# 17-eMMC_FLASH_SDCARD_INTERFACE.net
KiCad netlist of a schematic drawn in Altium Designer
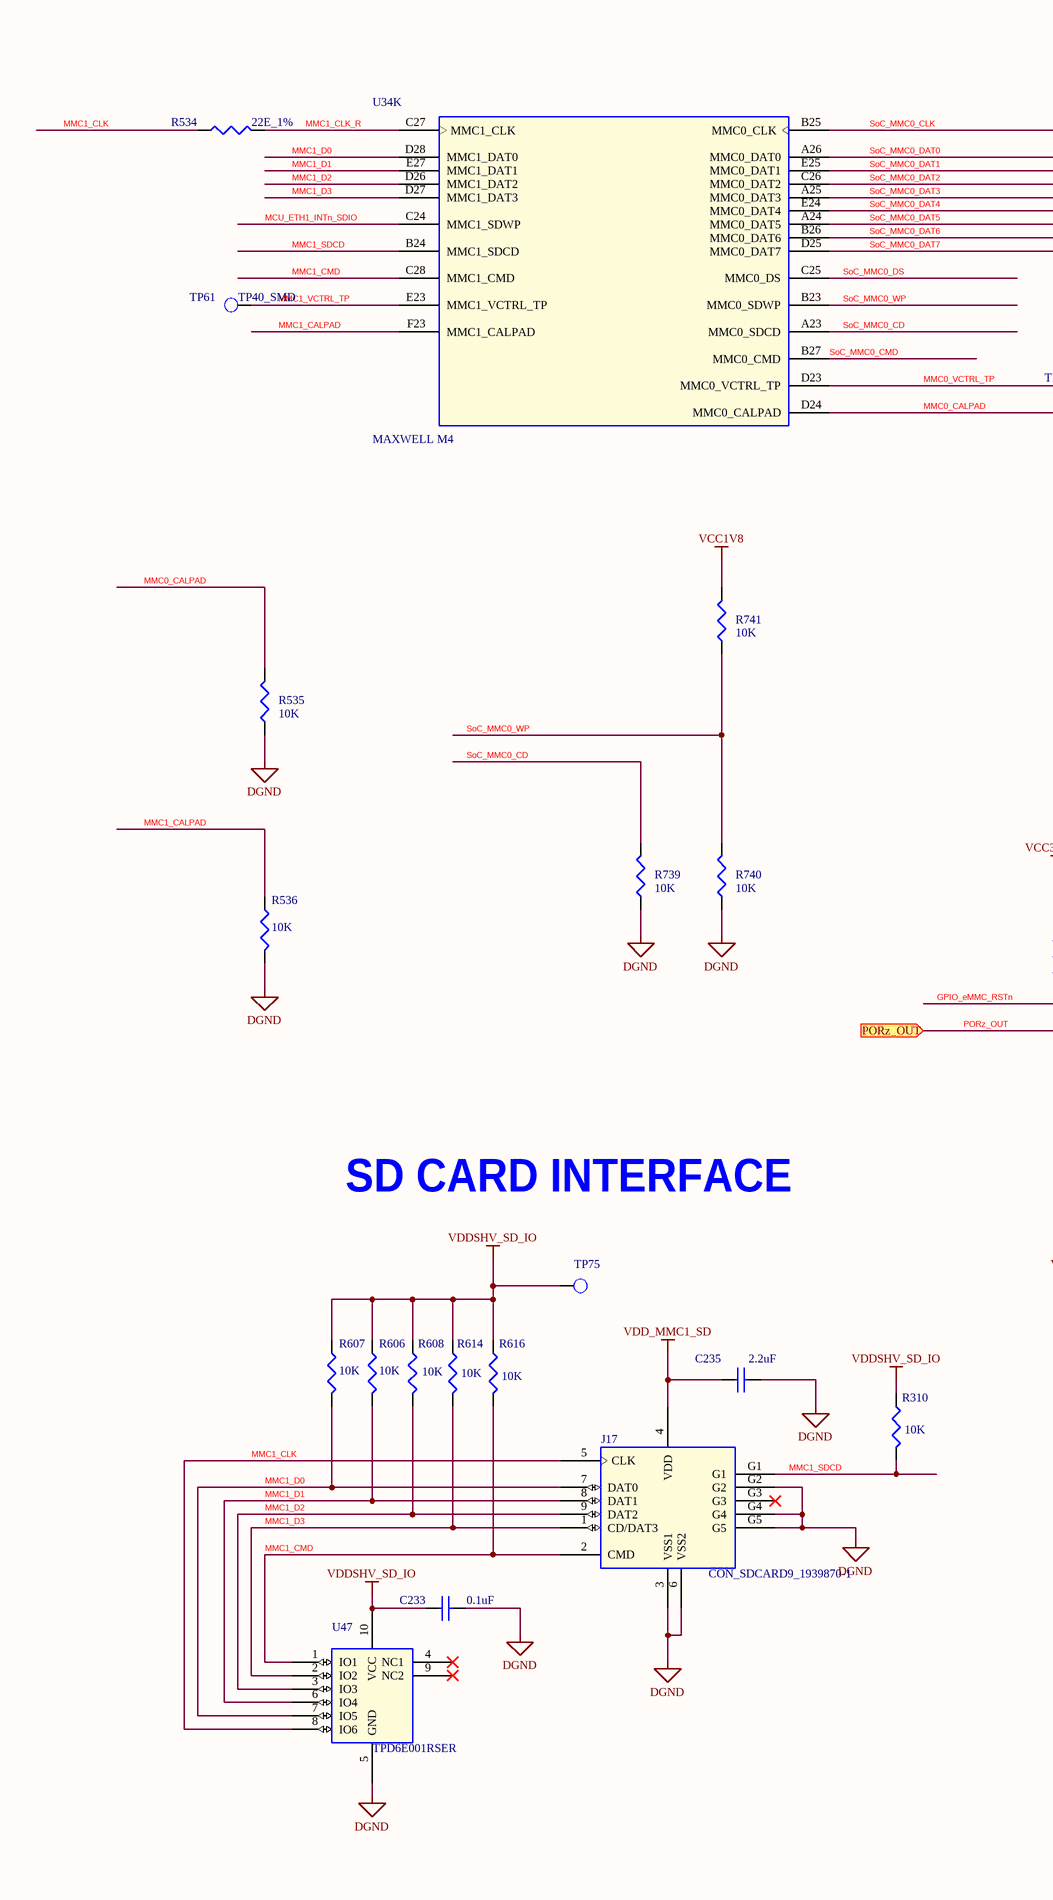
[diagram p0: 17-eMMC FLASH_SDCARD INTERFACE.SchDoc, left]
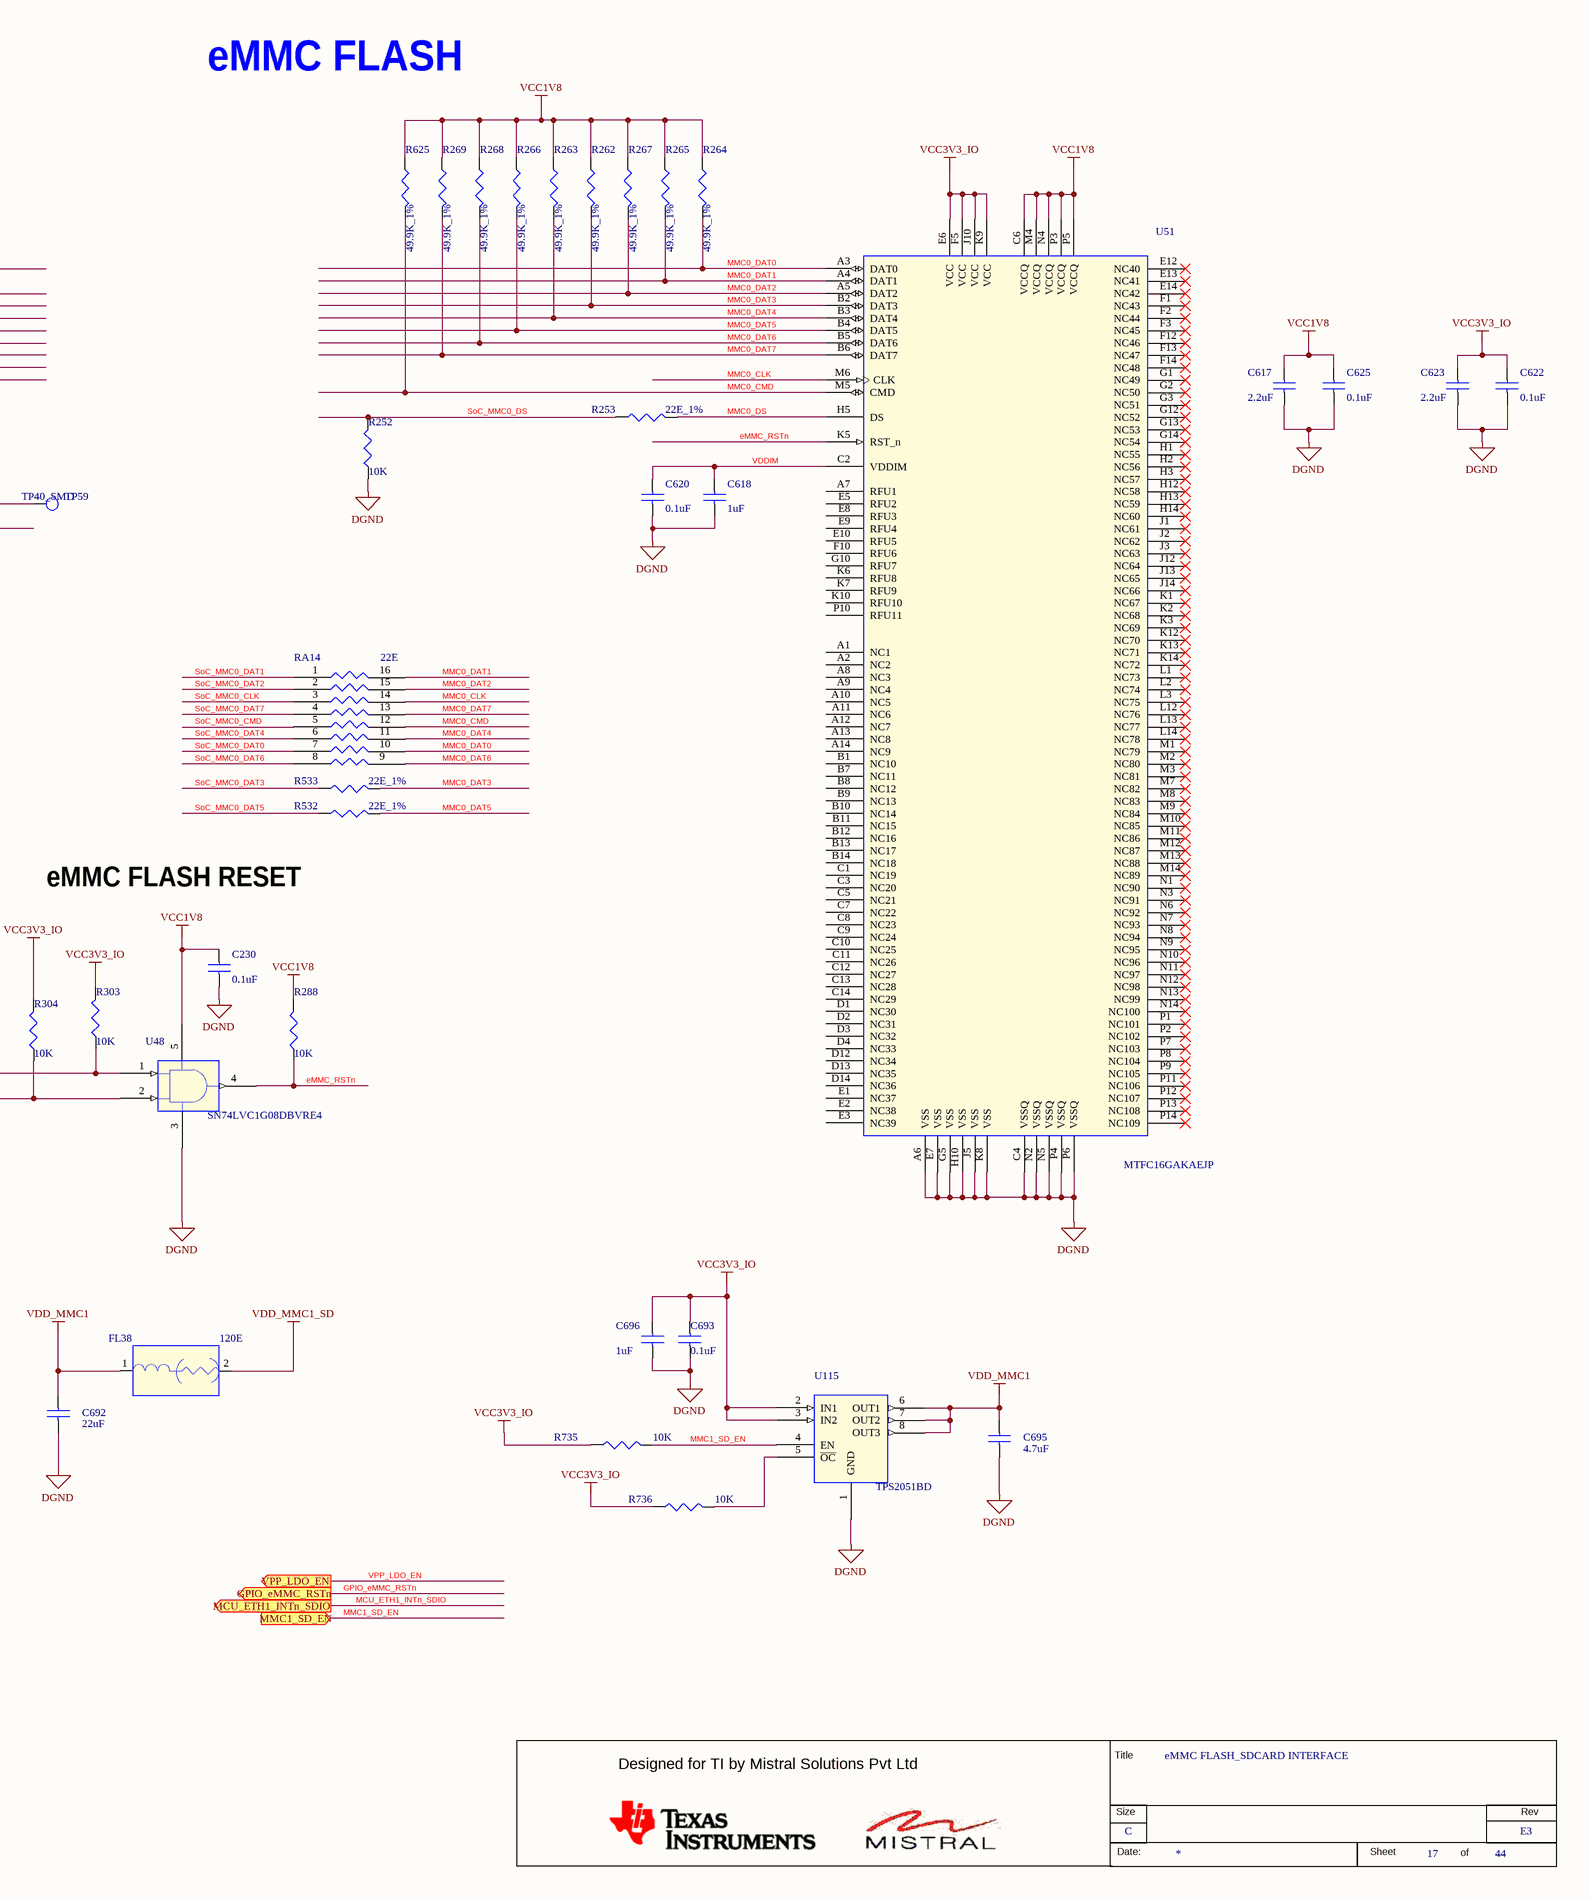
[diagram p1: 17-eMMC FLASH_SDCARD INTERFACE.SchDoc, right]

(export (version "E")
  (design (tool "Eeschema 10.0.6"))
  (components
    (comp (ref "C230")
      (value "0.1uF")
      (footprint "CAP0201_0-5")
      (description "CAP CERAMIC 0.1uF 16V 10% X5R 0201")
      (fields
        (field (name "MISTRAL PART NO") "120009030072-R")
        (field (name "MFR_PART_NUMBER") "GRM033R61C104KE84J")
      )
      (libsource (lib "*") (part "CAP_Dup5"))
    )
    (comp (ref "C233")
      (value "0.1uF")
      (footprint "CAP0201_0-5")
      (description "CAP CERAMIC 0.1uF 16V 10% X5R 0201")
      (fields (field (name "DISTRIBUTOR_PART_NUMBER") "490-16742-1-ND") (field (name "VOLTAGE") "16V"))
      (libsource (lib "*") (part "CAP_Dup5"))
    )
    (comp (ref "C235")
      (value "2.2uF")
      (footprint "CAP0402_0-75")
      (description "CAP CERAMIC 2.2uF 10V 20% X5R 0402")
      (fields
        (field (name "MISTRAL PART NO") "120018010016-R")
        (field (name "MFR_PART_NUMBER") "GRT155R61A225ME01D")
      )
      (libsource (lib "*") (part "CAP_Dup5"))
    )
    (comp (ref "C617")
      (value "2.2uF")
      (footprint "CAP0402_0-75")
      (description "CAP CERAMIC 2.2uF 10V 20% X5R 0402")
      (fields
        (field (name "MISTRAL PART NO") "120018010016-R")
        (field (name "MFR_PART_NUMBER") "GRT155R61A225ME01D")
      )
      (libsource (lib "*") (part "CAP_Dup5"))
    )
    (comp (ref "C618")
      (value "1uF")
      (footprint "CAP0402_0-75")
      (description "CAP CERAMIC 1uF 16V 20% X5R 0402")
      (fields (field (name "DISTRIBUTOR_PART_NUMBER") "587-5514-1-ND") (field (name "VOLTAGE") "16V"))
      (libsource (lib "*") (part "CAP_Dup5"))
    )
    (comp (ref "C620")
      (value "0.1uF")
      (footprint "CAP0201_0-5")
      (description "CAP CERAMIC 0.1uF 16V 10% X5R 0201")
      (fields
        (field (name "MISTRAL PART NO") "120009030072-R")
        (field (name "MFR_PART_NUMBER") "GRM033R61C104KE84J")
      )
      (libsource (lib "*") (part "CAP_Dup5"))
    )
    (comp (ref "C622")
      (value "0.1uF")
      (footprint "CAP0201_0-5")
      (description "CAP CERAMIC 0.1uF 16V 10% X5R 0201")
      (fields
        (field (name "MISTRAL PART NO") "120009030072-R")
        (field (name "MFR_PART_NUMBER") "GRM033R61C104KE84J")
      )
      (libsource (lib "*") (part "CAP_Dup5"))
    )
    (comp (ref "C623")
      (value "2.2uF")
      (footprint "CAP0402_0-75")
      (description "CAP CERAMIC 2.2uF 10V 20% X5R 0402")
      (fields
        (field (name "MISTRAL PART NO") "120018010016-R")
        (field (name "MFR_PART_NUMBER") "GRT155R61A225ME01D")
      )
      (libsource (lib "*") (part "CAP_Dup5"))
    )
    (comp (ref "C625")
      (value "0.1uF")
      (footprint "CAP0201_0-5")
      (description "CAP CERAMIC 0.1uF 16V 10% X5R 0201")
      (fields
        (field (name "MISTRAL PART NO") "120009030072-R")
        (field (name "MFR_PART_NUMBER") "GRM033R61C104KE84J")
      )
      (libsource (lib "*") (part "CAP_Dup5"))
    )
    (comp (ref "C692")
      (value "22uF")
      (footprint "CAP1206_2")
      (description "CAP CERAMIC 22uF 16V 20% X7R 1206")
      (fields (field (name "DISTRIBUTOR_PART_NUMBER") "587-4319-1-ND") (field (name "VOLTAGE") "16V"))
      (libsource (lib "*") (part "CAP_Dup5"))
    )
    (comp (ref "C693")
      (value "0.1uF")
      (footprint "CAP0201_0-5")
      (description "CAP CERAMIC 0.1uF 16V 10% X5R 0201")
      (fields (field (name "DISTRIBUTOR_PART_NUMBER") "490-16742-1-ND") (field (name "VOLTAGE") "16V"))
      (libsource (lib "*") (part "CAP_Dup5"))
    )
    (comp (ref "C695")
      (value "4.7uF")
      (footprint "CAP0402_0-75")
      (description "CAP CERAMIC 4.7uF 10V 20% X5R 0402")
      (fields
        (field (name "MISTRAL PART NO") "120012060002-R")
        (field (name "MFR_PART_NUMBER") "0402ZD475MAT2A")
      )
      (libsource (lib "*") (part "CAP_Dup5"))
    )
    (comp (ref "C696")
      (value "1uF")
      (footprint "CAP0402_0-75")
      (description "CAP CERAMIC 1uF 16V 20% X5R 0402")
      (fields (field (name "DISTRIBUTOR_PART_NUMBER") "587-5514-1-ND") (field (name "VOLTAGE") "16V"))
      (libsource (lib "*") (part "CAP_Dup5"))
    )
    (comp (ref "FL38")
      (value "120E")
      (footprint "EMIFIL_BLM15A_0402_0-6")
      (description "FERRITE CHIP 120E 1.3A 0402")
      (fields (field (name "DISTRIBUTOR_PART_NUMBER") "490-5203-1-ND") (field (name "VOLTAGE") "NA"))
      (libsource (lib "*") (part "EMIFILTER_IND"))
    )
    (comp (ref "J17")
      (value "CON_SDCARD9_1939870-1")
      (footprint "CON_SD9_1939870-1_S_R_S_2-9")
      (description "CON SD CARD PUSH-PUSH 9POS RT SMD")
      (fields (field (name "MISTRAL PART NO") "150017100004-R") (field (name "MFR_PART_NUMBER") "1939870-1"))
      (libsource (lib "*") (part "CON_SDCARD9_1939870-1"))
    )
    (comp (ref "R252")
      (value "10K")
      (footprint "RES0402_0-5")
      (description "RES 10K 1/16W 5% 0402")
      (fields (field (name "DISTRIBUTOR_PART_NUMBER") "311-10KJRCT-ND") (field (name "VOLTAGE") "NA"))
      (libsource (lib "*") (part "RESISTOR_Dup5"))
    )
    (comp (ref "R253")
      (value "22E_1%")
      (footprint "RES0402")
      (description "RES 22E 1/16W 1% 0402")
      (fields
        (field (name "CUST_PART_NUMBER") "4700-80047E")
        (field (name "DISTRIBUTOR_PART_NUMBER") "311-22.0LRCT-ND")
      )
      (libsource (lib "*") (part "RESISTOR_Dup4"))
    )
    (comp (ref "R262")
      (value "49.9K_1%")
      (footprint "RES0402")
      (description "RES 49.9K1/16W 1% 0402")
      (fields (field (name "DISTRIBUTOR_PART_NUMBER") "311-49.9KLRCT-ND") (field (name "TOLERANCE") "1%"))
      (libsource (lib "*") (part "RESISTOR_Dup5"))
    )
    (comp (ref "R263")
      (value "49.9K_1%")
      (footprint "RES0402")
      (description "RES 49.9K1/16W 1% 0402")
      (fields
        (field (name "MISTRAL PART NO") "110009030904-P")
        (field (name "MFR_PART_NUMBER") "RC0402FR-0749K9L")
      )
      (libsource (lib "*") (part "RESISTOR_Dup5"))
    )
    (comp (ref "R264")
      (value "49.9K_1%")
      (footprint "RES0402")
      (description "RES 49.9K1/16W 1% 0402")
      (fields
        (field (name "MISTRAL PART NO") "110009030904-P")
        (field (name "MFR_PART_NUMBER") "RC0402FR-0749K9L")
      )
      (libsource (lib "*") (part "RESISTOR_Dup5"))
    )
    (comp (ref "R265")
      (value "49.9K_1%")
      (footprint "RES0402")
      (description "RES 49.9K1/16W 1% 0402")
      (fields
        (field (name "MISTRAL PART NO") "110009030904-P")
        (field (name "MFR_PART_NUMBER") "RC0402FR-0749K9L")
      )
      (libsource (lib "*") (part "RESISTOR_Dup5"))
    )
    (comp (ref "R266")
      (value "49.9K_1%")
      (footprint "RES0402")
      (description "RES 49.9K1/16W 1% 0402")
      (fields (field (name "DISTRIBUTOR_PART_NUMBER") "311-49.9KLRCT-ND") (field (name "TOLERANCE") "1%"))
      (libsource (lib "*") (part "RESISTOR_Dup5"))
    )
    (comp (ref "R267")
      (value "49.9K_1%")
      (footprint "RES0402")
      (description "RES 49.9K1/16W 1% 0402")
      (fields (field (name "DISTRIBUTOR_PART_NUMBER") "311-49.9KLRCT-ND") (field (name "TOLERANCE") "1%"))
      (libsource (lib "*") (part "RESISTOR_Dup5"))
    )
    (comp (ref "R268")
      (value "49.9K_1%")
      (footprint "RES0402")
      (description "RES 49.9K1/16W 1% 0402")
      (fields
        (field (name "MISTRAL PART NO") "110009030904-P")
        (field (name "MFR_PART_NUMBER") "RC0402FR-0749K9L")
      )
      (libsource (lib "*") (part "RESISTOR_Dup5"))
    )
    (comp (ref "R269")
      (value "49.9K_1%")
      (footprint "RES0402")
      (description "RES 49.9K1/16W 1% 0402")
      (fields (field (name "DISTRIBUTOR_PART_NUMBER") "311-49.9KLRCT-ND") (field (name "TOLERANCE") "1%"))
      (libsource (lib "*") (part "RESISTOR_Dup5"))
    )
    (comp (ref "R288")
      (value "10K")
      (footprint "RES0402_0-5")
      (description "RES 10K 1/16W 5% 0402")
      (fields (field (name "DISTRIBUTOR_PART_NUMBER") "311-10KJRCT-ND") (field (name "VOLTAGE") "NA"))
      (libsource (lib "*") (part "RESISTOR_Dup5"))
    )
    (comp (ref "R303")
      (value "10K")
      (footprint "RES0402_0-5")
      (description "RES 10K 1/16W 5% 0402")
      (fields
        (field (name "MISTRAL PART NO") "110009030208-R")
        (field (name "MFR_PART_NUMBER") "RC0402JR-0710KL")
      )
      (libsource (lib "*") (part "RESISTOR_Dup5"))
    )
    (comp (ref "R304")
      (value "10K")
      (footprint "RES0402_0-5")
      (description "RES 10K 1/16W 5% 0402")
      (fields
        (field (name "MISTRAL PART NO") "110009030208-R")
        (field (name "MFR_PART_NUMBER") "RC0402JR-0710KL")
      )
      (libsource (lib "*") (part "RESISTOR_Dup5"))
    )
    (comp (ref "R310")
      (value "10K")
      (footprint "RES0402_0-5")
      (description "RES 10K 1/16W 5% 0402")
      (fields (field (name "DISTRIBUTOR_PART_NUMBER") "311-10KJRCT-ND") (field (name "VOLTAGE") "NA"))
      (libsource (lib "*") (part "RESISTOR_Dup5"))
    )
    (comp (ref "R532")
      (value "22E_1%")
      (footprint "RES0402")
      (description "RES 22E 1/16W 1% 0402")
      (fields
        (field (name "CUST_PART_NUMBER") "4700-80047E")
        (field (name "DISTRIBUTOR_PART_NUMBER") "311-22.0LRCT-ND")
      )
      (libsource (lib "*") (part "RESISTOR_Dup4"))
    )
    (comp (ref "R533")
      (value "22E_1%")
      (footprint "RES0402")
      (description "RES 22E 1/16W 1% 0402")
      (fields
        (field (name "CUST_PART_NUMBER") "4700-80047E")
        (field (name "DISTRIBUTOR_PART_NUMBER") "311-22.0LRCT-ND")
      )
      (libsource (lib "*") (part "RESISTOR_Dup4"))
    )
    (comp (ref "R534")
      (value "22E_1%")
      (footprint "RES0402")
      (description "RES 22E 1/16W 1% 0402")
      (fields
        (field (name "MISTRAL PART NO") "110009090004-P")
        (field (name "MFR_PART_NUMBER") "RC0402FR-0722RL")
      )
      (libsource (lib "*") (part "RESISTOR_Dup5"))
    )
    (comp (ref "R535")
      (value "10K")
      (footprint "RES0402_0-5")
      (description "RES 10K 1/16W 5% 0402")
      (fields (field (name "DISTRIBUTOR_PART_NUMBER") "311-10KJRCT-ND") (field (name "VOLTAGE") "NA"))
      (libsource (lib "*") (part "RESISTOR_Dup5"))
    )
    (comp (ref "R536")
      (value "10K")
      (footprint "RES0402_0-5")
      (description "RES 10K 1/16W 5% 0402")
      (fields
        (field (name "MISTRAL PART NO") "110009030208-R")
        (field (name "MFR_PART_NUMBER") "RC0402JR-0710KL")
      )
      (libsource (lib "*") (part "RESISTOR_Dup5"))
    )
    (comp (ref "R606")
      (value "10K")
      (footprint "RES0402_0-5")
      (description "RES 10K 1/16W 5% 0402")
      (fields
        (field (name "MISTRAL PART NO") "110009030208-R")
        (field (name "MFR_PART_NUMBER") "RC0402JR-0710KL")
      )
      (libsource (lib "*") (part "RESISTOR_Dup5"))
    )
    (comp (ref "R607")
      (value "10K")
      (footprint "RES0402_0-5")
      (description "RES 10K 1/16W 5% 0402")
      (fields
        (field (name "MISTRAL PART NO") "110009030208-R")
        (field (name "MFR_PART_NUMBER") "RC0402JR-0710KL")
      )
      (libsource (lib "*") (part "RESISTOR_Dup5"))
    )
    (comp (ref "R608")
      (value "10K")
      (footprint "RES0402_0-5")
      (description "RES 10K 1/16W 5% 0402")
      (fields (field (name "DISTRIBUTOR_PART_NUMBER") "311-10KJRCT-ND") (field (name "VOLTAGE") "NA"))
      (libsource (lib "*") (part "RESISTOR_Dup5"))
    )
    (comp (ref "R614")
      (value "10K")
      (footprint "RES0402_0-5")
      (description "RES 10K 1/16W 5% 0402")
      (fields (field (name "DISTRIBUTOR_PART_NUMBER") "311-10KJRCT-ND") (field (name "VOLTAGE") "NA"))
      (libsource (lib "*") (part "RESISTOR_Dup5"))
    )
    (comp (ref "R616")
      (value "10K")
      (footprint "RES0402_0-5")
      (description "RES 10K 1/16W 5% 0402")
      (fields
        (field (name "MISTRAL PART NO") "110009030208-R")
        (field (name "MFR_PART_NUMBER") "RC0402JR-0710KL")
      )
      (libsource (lib "*") (part "RESISTOR_Dup5"))
    )
    (comp (ref "R625")
      (value "49.9K_1%")
      (footprint "RES0402")
      (description "RES 49.9K1/16W 1% 0402")
      (fields
        (field (name "MISTRAL PART NO") "110009030904-P")
        (field (name "MFR_PART_NUMBER") "RC0402FR-0749K9L")
      )
      (libsource (lib "*") (part "RESISTOR_Dup5"))
    )
    (comp (ref "R735")
      (value "10K")
      (footprint "RES0402_0-5")
      (description "RES 10K 1/16W 5% 0402")
      (fields
        (field (name "MISTRAL PART NO") "110009030208-R")
        (field (name "MFR_PART_NUMBER") "RC0402JR-0710KL")
      )
      (libsource (lib "*") (part "RESISTOR_Dup5"))
    )
    (comp (ref "R736")
      (value "10K")
      (footprint "RES0402_0-5")
      (description "RES 10K 1/16W 5% 0402")
      (fields (field (name "DISTRIBUTOR_PART_NUMBER") "311-10KJRCT-ND") (field (name "VOLTAGE") "NA"))
      (libsource (lib "*") (part "RESISTOR_Dup5"))
    )
    (comp (ref "R739")
      (value "10K")
      (footprint "RES0402_0-5")
      (description "RES 10K 1/16W 5% 0402")
      (fields (field (name "DISTRIBUTOR_PART_NUMBER") "311-10KJRCT-ND") (field (name "VOLTAGE") "NA"))
      (libsource (lib "*") (part "RESISTOR_Dup5"))
    )
    (comp (ref "R740")
      (value "10K")
      (footprint "RES0402_0-5")
      (description "RES 10K 1/16W 5% 0402")
      (fields (field (name "DISTRIBUTOR_PART_NUMBER") "311-10KJRCT-ND") (field (name "VOLTAGE") "NA"))
      (libsource (lib "*") (part "RESISTOR_Dup5"))
    )
    (comp (ref "R741")
      (value "10K")
      (footprint "RES0402_0-5")
      (description "RES 10K 1/16W 5% 0402")
      (fields (field (name "DISTRIBUTOR_PART_NUMBER") "311-10KJRCT-ND") (field (name "VOLTAGE") "NA"))
      (libsource (lib "*") (part "RESISTOR_Dup5"))
    )
    (comp (ref "RA14")
      (value "22E")
      (footprint "RESA_0402-8")
      (description "RES ARRAY 22E 62.5mW 5% 0402")
      (fields
        (field (name "MISTRAL PART NO") "110009030020-R")
        (field (name "MFR_PART_NUMBER") "741X163220JP")
      )
      (libsource (lib "*") (part "RESARR_ISO8"))
    )
    (comp (ref "TP59")
      (value "TP40_SMD")
      (footprint "TP40_SMD")
      (description "TESTPOINT CIR 40 SMD")
      (fields (field (name "VOLTAGE") "NA") (field (name "MISTRAL PART NO") "130009030933"))
      (libsource (lib "*") (part "TESTPOINT"))
    )
    (comp (ref "TP61")
      (value "TP40_SMD")
      (footprint "TP40_SMD")
      (description "TESTPOINT CIR 40 SMD")
      (fields (field (name "VOLTAGE") "NA") (field (name "MISTRAL PART NO") "130009030933"))
      (libsource (lib "*") (part "TESTPOINT"))
    )
    (comp (ref "TP75")
      (value "TP40_SMD")
      (footprint "TP40_SMD")
      (description "TESTPOINT CIR 40 SMD")
      (fields (field (name "MISTRAL PART NO") "130009030933") (field (name "DISTRIBUTOR_PART_NUMBER") "NA"))
      (libsource (lib "*") (part "TESTPOINT"))
    )
    (comp (ref "U34")
      (value "MAXWELL M4")
      (footprint "BGA784_31-49_910X910_1-7")
      (description "IC MAXWELL MICRO CONTROLLER UNIT BGA784")
      (fields (field (name "DISTRIBUTOR_PART_NUMBER") "NA") (field (name "MFR_PART_NUMBER") "MAXWELL M4_EVM"))
      (libsource (lib "*") (part "AM654X_BGA784"))
    )
    (comp (ref "U47")
      (value "TPD6E001RSER")
      (footprint "UQFN10_19-68_80X60_0-6")
      (description "IC 6CH ESD-PROTECTION ARRAY UQFN10")
      (fields
        (field (name "MISTRAL PART NO") "141011080020-R")
        (field (name "TOLERANCE") "NA")
        (field (name "LIBRARY PATH") "Y~{:}MIS_DATABAS~{E}Librar~{y}ALTIUM_TOO~{L}SCHEMATICS_PART~{S}MS_MISCINTERFACE_Library.schlib")
      )
      (libsource (lib "*") (part "TPD6E001RSE_UQFN10"))
    )
    (comp (ref "U48")
      (value "SN74LVC1G08DBVRE4")
      (footprint "SOT23-5")
      (description "IC SINGLE 2-INPUT POSITIVE AND GATE SOT23-5")
      (fields
        (field (name "MISTRAL PART NO") "141009060026-R")
        (field (name "DISTRIBUTOR_PART_NUMBER") "SN74LVC1G08DBVRE4-ND")
      )
      (libsource (lib "*") (part "SN74LVC1G08DBVRE4_SOT23-5"))
    )
    (comp (ref "U51")
      (value "MTFC16GAKAEJP")
      (footprint "VFBGA153_19-68_460X520_1-2")
      (description "IC 16GB E-MMC MEMORY VFBGA153")
      (fields
        (field (name "MISTRAL PART NO") "141118010003-R")
        (field (name "MFR_PART_NUMBER") "MTFC16GAKAEJP-4M IT")
      )
      (libsource (lib "*") (part "MTFC16GAKAEJP_VFBGA153"))
    )
    (comp (ref "U115")
      (value "TPS2051BD")
      (footprint "SOIC8_1-8")
      (description "IC POWER DISTRIBUTION SWITCH SOIC8")
      (fields
        (field (name "MISTRAL PART NO") "142014060011-R")
        (field (name "TOLERANCE") "NA")
        (field (name "LIBRARY PATH") "Y~{:}MIS_DATABAS~{E}Librar~{y}ALTIUM_TOO~{L}SCHEMATICS_PART~{S}MS_MISCPOWER_Library.schlib")
      )
      (libsource (lib "*") (part "TPS2051BD_SOIC8"))
    )
  )
  (nets
    (net (code "1") (name "/GPIO_eMMC_RSTn") (class "Default")
      (node (ref "R303") (pin "1") (pinfunction "1_1") (pintype "passive"))
      (node (ref "U48") (pin "1") (pinfunction "A_1") (pintype "input"))
    )
    (net (code "2") (name "/MCU_ETH1_INTn_SDIO") (class "Default")
      (node (ref "U34") (pin "C24") (pinfunction "MMC1_SDWP_C24") (pintype "passive"))
    )
    (net (code "3") (name "/MMC0_CALPAD") (class "Default")
      (node (ref "R535") (pin "1") (pinfunction "1_1") (pintype "passive"))
      (node (ref "U34") (pin "D24") (pinfunction "MMC0_CALPAD_D24") (pintype "passive"))
    )
    (net (code "4") (name "/MMC0_CLK") (class "Default")
      (node (ref "RA14") (pin "14") (pinfunction "14_14") (pintype "passive"))
      (node (ref "U51") (pin "M6") (pinfunction "CLK_M6") (pintype "input"))
    )
    (net (code "5") (name "/MMC0_CMD") (class "Default")
      (node (ref "R625") (pin "2") (pinfunction "2_2") (pintype "passive"))
      (node (ref "RA14") (pin "12") (pinfunction "12_12") (pintype "passive"))
      (node (ref "U51") (pin "M5") (pinfunction "CMD_M5") (pintype "bidirectional"))
    )
    (net (code "6") (name "/MMC0_DAT0") (class "Default")
      (node (ref "R264") (pin "2") (pinfunction "2_2") (pintype "passive"))
      (node (ref "RA14") (pin "10") (pinfunction "10_10") (pintype "passive"))
      (node (ref "U51") (pin "A3") (pinfunction "DAT0_A3") (pintype "bidirectional"))
    )
    (net (code "7") (name "/MMC0_DAT1") (class "Default")
      (node (ref "R265") (pin "2") (pinfunction "2_2") (pintype "passive"))
      (node (ref "RA14") (pin "16") (pinfunction "16_16") (pintype "passive"))
      (node (ref "U51") (pin "A4") (pinfunction "DAT1_A4") (pintype "bidirectional"))
    )
    (net (code "8") (name "/MMC0_DAT2") (class "Default")
      (node (ref "R267") (pin "2") (pinfunction "2_2") (pintype "passive"))
      (node (ref "RA14") (pin "15") (pinfunction "15_15") (pintype "passive"))
      (node (ref "U51") (pin "A5") (pinfunction "DAT2_A5") (pintype "bidirectional"))
    )
    (net (code "9") (name "/MMC0_DAT3") (class "Default")
      (node (ref "R262") (pin "2") (pinfunction "2_2") (pintype "passive"))
      (node (ref "R533") (pin "2") (pinfunction "2_2") (pintype "passive"))
      (node (ref "U51") (pin "B2") (pinfunction "DAT3_B2") (pintype "bidirectional"))
    )
    (net (code "10") (name "/MMC0_DAT4") (class "Default")
      (node (ref "R263") (pin "2") (pinfunction "2_2") (pintype "passive"))
      (node (ref "RA14") (pin "11") (pinfunction "11_11") (pintype "passive"))
      (node (ref "U51") (pin "B3") (pinfunction "DAT4_B3") (pintype "bidirectional"))
    )
    (net (code "11") (name "/MMC0_DAT5") (class "Default")
      (node (ref "R266") (pin "2") (pinfunction "2_2") (pintype "passive"))
      (node (ref "R532") (pin "2") (pinfunction "2_2") (pintype "passive"))
      (node (ref "U51") (pin "B4") (pinfunction "DAT5_B4") (pintype "bidirectional"))
    )
    (net (code "12") (name "/MMC0_DAT6") (class "Default")
      (node (ref "R268") (pin "2") (pinfunction "2_2") (pintype "passive"))
      (node (ref "RA14") (pin "9") (pinfunction "9_9") (pintype "passive"))
      (node (ref "U51") (pin "B5") (pinfunction "DAT6_B5") (pintype "bidirectional"))
    )
    (net (code "13") (name "/MMC0_DAT7") (class "Default")
      (node (ref "R269") (pin "2") (pinfunction "2_2") (pintype "passive"))
      (node (ref "RA14") (pin "13") (pinfunction "13_13") (pintype "passive"))
      (node (ref "U51") (pin "B6") (pinfunction "DAT7_B6") (pintype "bidirectional"))
    )
    (net (code "14") (name "/MMC0_DS") (class "Default")
      (node (ref "R253") (pin "2") (pinfunction "2_2") (pintype "passive"))
      (node (ref "U51") (pin "H5") (pinfunction "DS_H5") (pintype "passive"))
    )
    (net (code "15") (name "/MMC0_VCTRL_TP") (class "Default")
      (node (ref "TP59") (pin "1") (pinfunction "TP_1") (pintype "passive"))
      (node (ref "U34") (pin "D23") (pinfunction "MMC0_VCTRL_TP_D23") (pintype "passive"))
    )
    (net (code "16") (name "/MMC1_CALPAD") (class "Default")
      (node (ref "R536") (pin "1") (pinfunction "1_1") (pintype "passive"))
      (node (ref "U34") (pin "F23") (pinfunction "MMC1_CALPAD_F23") (pintype "passive"))
    )
    (net (code "17") (name "/MMC1_CLK") (class "Default")
      (node (ref "J17") (pin "5") (pinfunction "CLK_5") (pintype "passive"))
      (node (ref "R534") (pin "1") (pinfunction "1_1") (pintype "passive"))
      (node (ref "U47") (pin "8") (pinfunction "IO6_8") (pintype "bidirectional"))
    )
    (net (code "18") (name "/MMC1_CLK_R") (class "Default")
      (node (ref "R534") (pin "2") (pinfunction "2_2") (pintype "passive"))
      (node (ref "U34") (pin "C27") (pinfunction "MMC1_CLK_C27") (pintype "passive"))
    )
    (net (code "19") (name "/MMC1_CMD") (class "Default")
      (node (ref "J17") (pin "2") (pinfunction "CMD_2") (pintype "passive"))
      (node (ref "R616") (pin "2") (pinfunction "2_2") (pintype "passive"))
      (node (ref "U34") (pin "C28") (pinfunction "MMC1_CMD_C28") (pintype "passive"))
      (node (ref "U47") (pin "1") (pinfunction "IO1_1") (pintype "bidirectional"))
    )
    (net (code "20") (name "/MMC1_D0") (class "Default")
      (node (ref "J17") (pin "7") (pinfunction "DAT0_7") (pintype "bidirectional"))
      (node (ref "R607") (pin "2") (pinfunction "2_2") (pintype "passive"))
      (node (ref "U34") (pin "D28") (pinfunction "MMC1_DAT0_D28") (pintype "passive"))
      (node (ref "U47") (pin "7") (pinfunction "IO5_7") (pintype "bidirectional"))
    )
    (net (code "21") (name "/MMC1_D1") (class "Default")
      (node (ref "J17") (pin "8") (pinfunction "DAT1_8") (pintype "bidirectional"))
      (node (ref "R606") (pin "2") (pinfunction "2_2") (pintype "passive"))
      (node (ref "U34") (pin "E27") (pinfunction "MMC1_DAT1_E27") (pintype "passive"))
      (node (ref "U47") (pin "6") (pinfunction "IO4_6") (pintype "bidirectional"))
    )
    (net (code "22") (name "/MMC1_D2") (class "Default")
      (node (ref "J17") (pin "9") (pinfunction "DAT2_9") (pintype "bidirectional"))
      (node (ref "R608") (pin "2") (pinfunction "2_2") (pintype "passive"))
      (node (ref "U34") (pin "D26") (pinfunction "MMC1_DAT2_D26") (pintype "passive"))
      (node (ref "U47") (pin "3") (pinfunction "IO3_3") (pintype "bidirectional"))
    )
    (net (code "23") (name "/MMC1_D3") (class "Default")
      (node (ref "J17") (pin "1") (pinfunction "CD/DAT3_1") (pintype "bidirectional"))
      (node (ref "R614") (pin "2") (pinfunction "2_2") (pintype "passive"))
      (node (ref "U34") (pin "D27") (pinfunction "MMC1_DAT3_D27") (pintype "passive"))
      (node (ref "U47") (pin "2") (pinfunction "IO2_2") (pintype "bidirectional"))
    )
    (net (code "24") (name "/MMC1_SDCD") (class "Default")
      (node (ref "J17") (pin "G1") (pinfunction "G1_G1") (pintype "passive"))
      (node (ref "R310") (pin "2") (pinfunction "2_2") (pintype "passive"))
      (node (ref "U34") (pin "B24") (pinfunction "MMC1_SDCD_B24") (pintype "passive"))
    )
    (net (code "25") (name "/MMC1_SD_EN") (class "Default")
      (node (ref "R735") (pin "2") (pinfunction "2_2") (pintype "passive"))
      (node (ref "U115") (pin "4") (pinfunction "EN_4") (pintype "passive"))
    )
    (net (code "26") (name "/MMC1_VCTRL_TP") (class "Default")
      (node (ref "TP61") (pin "1") (pinfunction "TP_1") (pintype "passive"))
      (node (ref "U34") (pin "E23") (pinfunction "MMC1_VCTRL_TP_E23") (pintype "passive"))
    )
    (net (code "27") (name "/PORz_OUT") (class "Default")
      (node (ref "R304") (pin "1") (pinfunction "1_1") (pintype "passive"))
      (node (ref "U48") (pin "2") (pinfunction "B_2") (pintype "input"))
    )
    (net (code "28") (name "/SoC_MMC0_CD") (class "Default")
      (node (ref "R739") (pin "1") (pinfunction "1_1") (pintype "passive"))
      (node (ref "U34") (pin "A23") (pinfunction "MMC0_SDCD_A23") (pintype "passive"))
    )
    (net (code "29") (name "/SoC_MMC0_CLK") (class "Default")
      (node (ref "RA14") (pin "3") (pinfunction "3_3") (pintype "passive"))
      (node (ref "U34") (pin "B25") (pinfunction "MMC0_CLK_B25") (pintype "passive"))
    )
    (net (code "30") (name "/SoC_MMC0_CMD") (class "Default")
      (node (ref "RA14") (pin "5") (pinfunction "5_5") (pintype "passive"))
      (node (ref "U34") (pin "B27") (pinfunction "MMC0_CMD_B27") (pintype "passive"))
    )
    (net (code "31") (name "/SoC_MMC0_DAT0") (class "Default")
      (node (ref "RA14") (pin "7") (pinfunction "7_7") (pintype "passive"))
      (node (ref "U34") (pin "A26") (pinfunction "MMC0_DAT0_A26") (pintype "passive"))
    )
    (net (code "32") (name "/SoC_MMC0_DAT1") (class "Default")
      (node (ref "RA14") (pin "1") (pinfunction "1_1") (pintype "passive"))
      (node (ref "U34") (pin "E25") (pinfunction "MMC0_DAT1_E25") (pintype "passive"))
    )
    (net (code "33") (name "/SoC_MMC0_DAT2") (class "Default")
      (node (ref "RA14") (pin "2") (pinfunction "2_2") (pintype "passive"))
      (node (ref "U34") (pin "C26") (pinfunction "MMC0_DAT2_C26") (pintype "passive"))
    )
    (net (code "34") (name "/SoC_MMC0_DAT3") (class "Default")
      (node (ref "R533") (pin "1") (pinfunction "1_1") (pintype "passive"))
      (node (ref "U34") (pin "A25") (pinfunction "MMC0_DAT3_A25") (pintype "passive"))
    )
    (net (code "35") (name "/SoC_MMC0_DAT4") (class "Default")
      (node (ref "RA14") (pin "6") (pinfunction "6_6") (pintype "passive"))
      (node (ref "U34") (pin "E24") (pinfunction "MMC0_DAT4_E24") (pintype "passive"))
    )
    (net (code "36") (name "/SoC_MMC0_DAT5") (class "Default")
      (node (ref "R532") (pin "1") (pinfunction "1_1") (pintype "passive"))
      (node (ref "U34") (pin "A24") (pinfunction "MMC0_DAT5_A24") (pintype "passive"))
    )
    (net (code "37") (name "/SoC_MMC0_DAT6") (class "Default")
      (node (ref "RA14") (pin "8") (pinfunction "8_8") (pintype "passive"))
      (node (ref "U34") (pin "B26") (pinfunction "MMC0_DAT6_B26") (pintype "passive"))
    )
    (net (code "38") (name "/SoC_MMC0_DAT7") (class "Default")
      (node (ref "RA14") (pin "4") (pinfunction "4_4") (pintype "passive"))
      (node (ref "U34") (pin "D25") (pinfunction "MMC0_DAT7_D25") (pintype "passive"))
    )
    (net (code "39") (name "/SoC_MMC0_DS") (class "Default")
      (node (ref "R252") (pin "2") (pinfunction "2_2") (pintype "passive"))
      (node (ref "R253") (pin "1") (pinfunction "1_1") (pintype "passive"))
      (node (ref "U34") (pin "C25") (pinfunction "MMC0_DS_C25") (pintype "passive"))
    )
    (net (code "40") (name "/SoC_MMC0_WP") (class "Default")
      (node (ref "R740") (pin "1") (pinfunction "1_1") (pintype "passive"))
      (node (ref "R741") (pin "2") (pinfunction "2_2") (pintype "passive"))
      (node (ref "U34") (pin "B23") (pinfunction "MMC0_SDWP_B23") (pintype "passive"))
    )
    (net (code "41") (name "/VDDIM") (class "Default")
      (node (ref "C618") (pin "1") (pinfunction "1_1") (pintype "passive"))
      (node (ref "C620") (pin "1") (pinfunction "1_1") (pintype "passive"))
      (node (ref "U51") (pin "C2") (pinfunction "VDDIM_C2") (pintype "passive"))
    )
    (net (code "43") (name "/eMMC_RSTn") (class "Default")
      (node (ref "R288") (pin "1") (pinfunction "1_1") (pintype "passive"))
      (node (ref "U48") (pin "4") (pinfunction "Y_4") (pintype "output"))
      (node (ref "U51") (pin "K5") (pinfunction "RST_n_K5") (pintype "input"))
    )
    (net (code "44") (name "DGND") (class "Default")
      (node (ref "C230") (pin "2") (pinfunction "2_2") (pintype "passive"))
      (node (ref "C233") (pin "2") (pinfunction "2_2") (pintype "passive"))
      (node (ref "C235") (pin "2") (pinfunction "2_2") (pintype "passive"))
      (node (ref "C617") (pin "2") (pinfunction "2_2") (pintype "passive"))
      (node (ref "C618") (pin "2") (pinfunction "2_2") (pintype "passive"))
      (node (ref "C620") (pin "2") (pinfunction "2_2") (pintype "passive"))
      (node (ref "C622") (pin "2") (pinfunction "2_2") (pintype "passive"))
      (node (ref "C623") (pin "2") (pinfunction "2_2") (pintype "passive"))
      (node (ref "C625") (pin "2") (pinfunction "2_2") (pintype "passive"))
      (node (ref "C692") (pin "2") (pinfunction "2_2") (pintype "passive"))
      (node (ref "C693") (pin "2") (pinfunction "2_2") (pintype "passive"))
      (node (ref "C695") (pin "2") (pinfunction "2_2") (pintype "passive"))
      (node (ref "C696") (pin "2") (pinfunction "2_2") (pintype "passive"))
      (node (ref "J17") (pin "3") (pinfunction "VSS1_3") (pintype "power_in"))
      (node (ref "J17") (pin "6") (pinfunction "VSS2_6") (pintype "power_in"))
      (node (ref "J17") (pin "G2") (pinfunction "G2_G2") (pintype "passive"))
      (node (ref "J17") (pin "G4") (pinfunction "G4_G4") (pintype "passive"))
      (node (ref "J17") (pin "G5") (pinfunction "G5_G5") (pintype "passive"))
      (node (ref "R252") (pin "1") (pinfunction "1_1") (pintype "passive"))
      (node (ref "R535") (pin "2") (pinfunction "2_2") (pintype "passive"))
      (node (ref "R536") (pin "2") (pinfunction "2_2") (pintype "passive"))
      (node (ref "R739") (pin "2") (pinfunction "2_2") (pintype "passive"))
      (node (ref "R740") (pin "2") (pinfunction "2_2") (pintype "passive"))
      (node (ref "U115") (pin "1") (pinfunction "GND_1") (pintype "power_in"))
      (node (ref "U47") (pin "5") (pinfunction "GND_5") (pintype "power_in"))
      (node (ref "U48") (pin "3") (pinfunction "GND_3") (pintype "power_in"))
      (node (ref "U51") (pin "A6") (pinfunction "VSS_A6") (pintype "power_in"))
      (node (ref "U51") (pin "C4") (pinfunction "VSSQ_C4") (pintype "power_in"))
      (node (ref "U51") (pin "E7") (pinfunction "VSS_E7") (pintype "power_in"))
      (node (ref "U51") (pin "G5") (pinfunction "VSS_G5") (pintype "power_in"))
      (node (ref "U51") (pin "H10") (pinfunction "VSS_H10") (pintype "power_in"))
      (node (ref "U51") (pin "J5") (pinfunction "VSS_J5") (pintype "power_in"))
      (node (ref "U51") (pin "K8") (pinfunction "VSS_K8") (pintype "power_in"))
      (node (ref "U51") (pin "N2") (pinfunction "VSSQ_N2") (pintype "power_in"))
      (node (ref "U51") (pin "N5") (pinfunction "VSSQ_N5") (pintype "power_in"))
      (node (ref "U51") (pin "P4") (pinfunction "VSSQ_P4") (pintype "power_in"))
      (node (ref "U51") (pin "P6") (pinfunction "VSSQ_P6") (pintype "power_in"))
    )
    (net (code "45") (name "Net-(U115-~{OC})") (class "Default")
      (node (ref "R736") (pin "2") (pinfunction "2_2") (pintype "passive"))
      (node (ref "U115") (pin "5") (pinfunction "~{OC}_5") (pintype "passive"))
    )
    (net (code "46") (name "VCC1V8") (class "Default")
      (node (ref "C230") (pin "1") (pinfunction "1_1") (pintype "passive"))
      (node (ref "C617") (pin "1") (pinfunction "1_1") (pintype "passive"))
      (node (ref "C625") (pin "1") (pinfunction "1_1") (pintype "passive"))
      (node (ref "R262") (pin "1") (pinfunction "1_1") (pintype "passive"))
      (node (ref "R263") (pin "1") (pinfunction "1_1") (pintype "passive"))
      (node (ref "R264") (pin "1") (pinfunction "1_1") (pintype "passive"))
      (node (ref "R265") (pin "1") (pinfunction "1_1") (pintype "passive"))
      (node (ref "R266") (pin "1") (pinfunction "1_1") (pintype "passive"))
      (node (ref "R267") (pin "1") (pinfunction "1_1") (pintype "passive"))
      (node (ref "R268") (pin "1") (pinfunction "1_1") (pintype "passive"))
      (node (ref "R269") (pin "1") (pinfunction "1_1") (pintype "passive"))
      (node (ref "R288") (pin "2") (pinfunction "2_2") (pintype "passive"))
      (node (ref "R625") (pin "1") (pinfunction "1_1") (pintype "passive"))
      (node (ref "R741") (pin "1") (pinfunction "1_1") (pintype "passive"))
      (node (ref "U48") (pin "5") (pinfunction "VCC_5") (pintype "power_in"))
      (node (ref "U51") (pin "C6") (pinfunction "VCCQ_C6") (pintype "power_in"))
      (node (ref "U51") (pin "M4") (pinfunction "VCCQ_M4") (pintype "power_in"))
      (node (ref "U51") (pin "N4") (pinfunction "VCCQ_N4") (pintype "power_in"))
      (node (ref "U51") (pin "P3") (pinfunction "VCCQ_P3") (pintype "power_in"))
      (node (ref "U51") (pin "P5") (pinfunction "VCCQ_P5") (pintype "power_in"))
    )
    (net (code "47") (name "VCC3V3_IO") (class "Default")
      (node (ref "C622") (pin "1") (pinfunction "1_1") (pintype "passive"))
      (node (ref "C623") (pin "1") (pinfunction "1_1") (pintype "passive"))
      (node (ref "C693") (pin "1") (pinfunction "1_1") (pintype "passive"))
      (node (ref "C696") (pin "1") (pinfunction "1_1") (pintype "passive"))
      (node (ref "R303") (pin "2") (pinfunction "2_2") (pintype "passive"))
      (node (ref "R304") (pin "2") (pinfunction "2_2") (pintype "passive"))
      (node (ref "R735") (pin "1") (pinfunction "1_1") (pintype "passive"))
      (node (ref "R736") (pin "1") (pinfunction "1_1") (pintype "passive"))
      (node (ref "U115") (pin "2") (pinfunction "IN1_2") (pintype "input"))
      (node (ref "U115") (pin "3") (pinfunction "IN2_3") (pintype "input"))
      (node (ref "U51") (pin "E6") (pinfunction "VCC_E6") (pintype "power_in"))
      (node (ref "U51") (pin "F5") (pinfunction "VCC_F5") (pintype "power_in"))
      (node (ref "U51") (pin "J10") (pinfunction "VCC_J10") (pintype "power_in"))
      (node (ref "U51") (pin "K9") (pinfunction "VCC_K9") (pintype "power_in"))
    )
    (net (code "48") (name "VDDSHV_SD_IO") (class "Default")
      (node (ref "C233") (pin "1") (pinfunction "1_1") (pintype "passive"))
      (node (ref "R310") (pin "1") (pinfunction "1_1") (pintype "passive"))
      (node (ref "R606") (pin "1") (pinfunction "1_1") (pintype "passive"))
      (node (ref "R607") (pin "1") (pinfunction "1_1") (pintype "passive"))
      (node (ref "R608") (pin "1") (pinfunction "1_1") (pintype "passive"))
      (node (ref "R614") (pin "1") (pinfunction "1_1") (pintype "passive"))
      (node (ref "R616") (pin "1") (pinfunction "1_1") (pintype "passive"))
      (node (ref "TP75") (pin "1") (pinfunction "TP_1") (pintype "passive"))
      (node (ref "U47") (pin "10") (pinfunction "VCC_10") (pintype "power_in"))
    )
    (net (code "49") (name "VDD_MMC1") (class "Default")
      (node (ref "C692") (pin "1") (pinfunction "1_1") (pintype "passive"))
      (node (ref "C695") (pin "1") (pinfunction "1_1") (pintype "passive"))
      (node (ref "FL38") (pin "1") (pinfunction "1_1") (pintype "passive"))
      (node (ref "U115") (pin "6") (pinfunction "OUT1_6") (pintype "output"))
      (node (ref "U115") (pin "7") (pinfunction "OUT2_7") (pintype "output"))
      (node (ref "U115") (pin "8") (pinfunction "OUT3_8") (pintype "output"))
    )
    (net (code "50") (name "VDD_MMC1_SD") (class "Default")
      (node (ref "C235") (pin "1") (pinfunction "1_1") (pintype "passive"))
      (node (ref "FL38") (pin "2") (pinfunction "2_2") (pintype "passive"))
      (node (ref "J17") (pin "4") (pinfunction "VDD_4") (pintype "power_in"))
    )
    (net (code "51") (name "unconnected-(J17-PadG3)") (class "Default")
      (node (ref "J17") (pin "G3") (pinfunction "G3_G3") (pintype "passive+no_connect"))
    )
    (net (code "52") (name "unconnected-(U47-NC1-Pad4)") (class "Default")
      (node (ref "U47") (pin "4") (pinfunction "NC1_4") (pintype "passive+no_connect"))
    )
    (net (code "53") (name "unconnected-(U47-NC2-Pad9)") (class "Default")
      (node (ref "U47") (pin "9") (pinfunction "NC2_9") (pintype "passive+no_connect"))
    )
    (net (code "54") (name "unconnected-(U51-NC1-PadA1)") (class "Default")
      (node (ref "U51") (pin "A1") (pinfunction "NC1_A1") (pintype "passive"))
    )
    (net (code "55") (name "unconnected-(U51-NC2-PadA2)") (class "Default")
      (node (ref "U51") (pin "A2") (pinfunction "NC2_A2") (pintype "passive"))
    )
    (net (code "56") (name "unconnected-(U51-NC3-PadA8)") (class "Default")
      (node (ref "U51") (pin "A8") (pinfunction "NC3_A8") (pintype "passive"))
    )
    (net (code "57") (name "unconnected-(U51-NC4-PadA9)") (class "Default")
      (node (ref "U51") (pin "A9") (pinfunction "NC4_A9") (pintype "passive"))
    )
    (net (code "58") (name "unconnected-(U51-NC5-PadA10)") (class "Default")
      (node (ref "U51") (pin "A10") (pinfunction "NC5_A10") (pintype "passive"))
    )
    (net (code "59") (name "unconnected-(U51-NC6-PadA11)") (class "Default")
      (node (ref "U51") (pin "A11") (pinfunction "NC6_A11") (pintype "passive"))
    )
    (net (code "60") (name "unconnected-(U51-NC7-PadA12)") (class "Default")
      (node (ref "U51") (pin "A12") (pinfunction "NC7_A12") (pintype "passive"))
    )
    (net (code "61") (name "unconnected-(U51-NC8-PadA13)") (class "Default")
      (node (ref "U51") (pin "A13") (pinfunction "NC8_A13") (pintype "passive"))
    )
    (net (code "62") (name "unconnected-(U51-NC9-PadA14)") (class "Default")
      (node (ref "U51") (pin "A14") (pinfunction "NC9_A14") (pintype "passive"))
    )
    (net (code "63") (name "unconnected-(U51-NC10-PadB1)") (class "Default")
      (node (ref "U51") (pin "B1") (pinfunction "NC10_B1") (pintype "passive"))
    )
    (net (code "64") (name "unconnected-(U51-NC11-PadB7)") (class "Default")
      (node (ref "U51") (pin "B7") (pinfunction "NC11_B7") (pintype "passive"))
    )
    (net (code "65") (name "unconnected-(U51-NC12-PadB8)") (class "Default")
      (node (ref "U51") (pin "B8") (pinfunction "NC12_B8") (pintype "passive"))
    )
    (net (code "66") (name "unconnected-(U51-NC13-PadB9)") (class "Default")
      (node (ref "U51") (pin "B9") (pinfunction "NC13_B9") (pintype "passive"))
    )
    (net (code "67") (name "unconnected-(U51-NC14-PadB10)") (class "Default")
      (node (ref "U51") (pin "B10") (pinfunction "NC14_B10") (pintype "passive"))
    )
    (net (code "68") (name "unconnected-(U51-NC15-PadB11)") (class "Default")
      (node (ref "U51") (pin "B11") (pinfunction "NC15_B11") (pintype "passive"))
    )
    (net (code "69") (name "unconnected-(U51-NC16-PadB12)") (class "Default")
      (node (ref "U51") (pin "B12") (pinfunction "NC16_B12") (pintype "passive"))
    )
    (net (code "70") (name "unconnected-(U51-NC17-PadB13)") (class "Default")
      (node (ref "U51") (pin "B13") (pinfunction "NC17_B13") (pintype "passive"))
    )
    (net (code "71") (name "unconnected-(U51-NC18-PadB14)") (class "Default")
      (node (ref "U51") (pin "B14") (pinfunction "NC18_B14") (pintype "passive"))
    )
    (net (code "72") (name "unconnected-(U51-NC19-PadC1)") (class "Default")
      (node (ref "U51") (pin "C1") (pinfunction "NC19_C1") (pintype "passive"))
    )
    (net (code "73") (name "unconnected-(U51-NC20-PadC3)") (class "Default")
      (node (ref "U51") (pin "C3") (pinfunction "NC20_C3") (pintype "passive"))
    )
    (net (code "74") (name "unconnected-(U51-NC21-PadC5)") (class "Default")
      (node (ref "U51") (pin "C5") (pinfunction "NC21_C5") (pintype "passive"))
    )
    (net (code "75") (name "unconnected-(U51-NC22-PadC7)") (class "Default")
      (node (ref "U51") (pin "C7") (pinfunction "NC22_C7") (pintype "passive"))
    )
    (net (code "76") (name "unconnected-(U51-NC23-PadC8)") (class "Default")
      (node (ref "U51") (pin "C8") (pinfunction "NC23_C8") (pintype "passive"))
    )
    (net (code "77") (name "unconnected-(U51-NC24-PadC9)") (class "Default")
      (node (ref "U51") (pin "C9") (pinfunction "NC24_C9") (pintype "passive"))
    )
    (net (code "78") (name "unconnected-(U51-NC25-PadC10)") (class "Default")
      (node (ref "U51") (pin "C10") (pinfunction "NC25_C10") (pintype "passive"))
    )
    (net (code "79") (name "unconnected-(U51-NC26-PadC11)") (class "Default")
      (node (ref "U51") (pin "C11") (pinfunction "NC26_C11") (pintype "passive"))
    )
    (net (code "80") (name "unconnected-(U51-NC27-PadC12)") (class "Default")
      (node (ref "U51") (pin "C12") (pinfunction "NC27_C12") (pintype "passive"))
    )
    (net (code "81") (name "unconnected-(U51-NC28-PadC13)") (class "Default")
      (node (ref "U51") (pin "C13") (pinfunction "NC28_C13") (pintype "passive"))
    )
    (net (code "82") (name "unconnected-(U51-NC29-PadC14)") (class "Default")
      (node (ref "U51") (pin "C14") (pinfunction "NC29_C14") (pintype "passive"))
    )
    (net (code "83") (name "unconnected-(U51-NC30-PadD1)") (class "Default")
      (node (ref "U51") (pin "D1") (pinfunction "NC30_D1") (pintype "passive"))
    )
    (net (code "84") (name "unconnected-(U51-NC31-PadD2)") (class "Default")
      (node (ref "U51") (pin "D2") (pinfunction "NC31_D2") (pintype "passive"))
    )
    (net (code "85") (name "unconnected-(U51-NC32-PadD3)") (class "Default")
      (node (ref "U51") (pin "D3") (pinfunction "NC32_D3") (pintype "passive"))
    )
    (net (code "86") (name "unconnected-(U51-NC33-PadD4)") (class "Default")
      (node (ref "U51") (pin "D4") (pinfunction "NC33_D4") (pintype "passive"))
    )
    (net (code "87") (name "unconnected-(U51-NC34-PadD12)") (class "Default")
      (node (ref "U51") (pin "D12") (pinfunction "NC34_D12") (pintype "passive"))
    )
    (net (code "88") (name "unconnected-(U51-NC35-PadD13)") (class "Default")
      (node (ref "U51") (pin "D13") (pinfunction "NC35_D13") (pintype "passive"))
    )
    (net (code "89") (name "unconnected-(U51-NC36-PadD14)") (class "Default")
      (node (ref "U51") (pin "D14") (pinfunction "NC36_D14") (pintype "passive"))
    )
    (net (code "90") (name "unconnected-(U51-NC37-PadE1)") (class "Default")
      (node (ref "U51") (pin "E1") (pinfunction "NC37_E1") (pintype "passive"))
    )
    (net (code "91") (name "unconnected-(U51-NC38-PadE2)") (class "Default")
      (node (ref "U51") (pin "E2") (pinfunction "NC38_E2") (pintype "passive"))
    )
    (net (code "92") (name "unconnected-(U51-NC39-PadE3)") (class "Default")
      (node (ref "U51") (pin "E3") (pinfunction "NC39_E3") (pintype "passive"))
    )
    (net (code "93") (name "unconnected-(U51-NC40-PadE12)") (class "Default")
      (node (ref "U51") (pin "E12") (pinfunction "NC40_E12") (pintype "passive+no_connect"))
    )
    (net (code "94") (name "unconnected-(U51-NC41-PadE13)") (class "Default")
      (node (ref "U51") (pin "E13") (pinfunction "NC41_E13") (pintype "passive+no_connect"))
    )
    (net (code "95") (name "unconnected-(U51-NC42-PadE14)") (class "Default")
      (node (ref "U51") (pin "E14") (pinfunction "NC42_E14") (pintype "passive+no_connect"))
    )
    (net (code "96") (name "unconnected-(U51-NC43-PadF1)") (class "Default")
      (node (ref "U51") (pin "F1") (pinfunction "NC43_F1") (pintype "passive+no_connect"))
    )
    (net (code "97") (name "unconnected-(U51-NC44-PadF2)") (class "Default")
      (node (ref "U51") (pin "F2") (pinfunction "NC44_F2") (pintype "passive+no_connect"))
    )
    (net (code "98") (name "unconnected-(U51-NC45-PadF3)") (class "Default")
      (node (ref "U51") (pin "F3") (pinfunction "NC45_F3") (pintype "passive+no_connect"))
    )
    (net (code "99") (name "unconnected-(U51-NC46-PadF12)") (class "Default")
      (node (ref "U51") (pin "F12") (pinfunction "NC46_F12") (pintype "passive+no_connect"))
    )
    (net (code "100") (name "unconnected-(U51-NC47-PadF13)") (class "Default")
      (node (ref "U51") (pin "F13") (pinfunction "NC47_F13") (pintype "passive+no_connect"))
    )
    (net (code "101") (name "unconnected-(U51-NC48-PadF14)") (class "Default")
      (node (ref "U51") (pin "F14") (pinfunction "NC48_F14") (pintype "passive+no_connect"))
    )
    (net (code "102") (name "unconnected-(U51-NC49-PadG1)") (class "Default")
      (node (ref "U51") (pin "G1") (pinfunction "NC49_G1") (pintype "passive+no_connect"))
    )
    (net (code "103") (name "unconnected-(U51-NC50-PadG2)") (class "Default")
      (node (ref "U51") (pin "G2") (pinfunction "NC50_G2") (pintype "passive+no_connect"))
    )
    (net (code "104") (name "unconnected-(U51-NC51-PadG3)") (class "Default")
      (node (ref "U51") (pin "G3") (pinfunction "NC51_G3") (pintype "passive+no_connect"))
    )
    (net (code "105") (name "unconnected-(U51-NC52-PadG12)") (class "Default")
      (node (ref "U51") (pin "G12") (pinfunction "NC52_G12") (pintype "passive+no_connect"))
    )
    (net (code "106") (name "unconnected-(U51-NC53-PadG13)") (class "Default")
      (node (ref "U51") (pin "G13") (pinfunction "NC53_G13") (pintype "passive+no_connect"))
    )
    (net (code "107") (name "unconnected-(U51-NC54-PadG14)") (class "Default")
      (node (ref "U51") (pin "G14") (pinfunction "NC54_G14") (pintype "passive+no_connect"))
    )
    (net (code "108") (name "unconnected-(U51-NC55-PadH1)") (class "Default")
      (node (ref "U51") (pin "H1") (pinfunction "NC55_H1") (pintype "passive+no_connect"))
    )
    (net (code "109") (name "unconnected-(U51-NC56-PadH2)") (class "Default")
      (node (ref "U51") (pin "H2") (pinfunction "NC56_H2") (pintype "passive+no_connect"))
    )
    (net (code "110") (name "unconnected-(U51-NC57-PadH3)") (class "Default")
      (node (ref "U51") (pin "H3") (pinfunction "NC57_H3") (pintype "passive+no_connect"))
    )
    (net (code "111") (name "unconnected-(U51-NC58-PadH12)") (class "Default")
      (node (ref "U51") (pin "H12") (pinfunction "NC58_H12") (pintype "passive+no_connect"))
    )
    (net (code "112") (name "unconnected-(U51-NC59-PadH13)") (class "Default")
      (node (ref "U51") (pin "H13") (pinfunction "NC59_H13") (pintype "passive+no_connect"))
    )
    (net (code "113") (name "unconnected-(U51-NC60-PadH14)") (class "Default")
      (node (ref "U51") (pin "H14") (pinfunction "NC60_H14") (pintype "passive+no_connect"))
    )
    (net (code "114") (name "unconnected-(U51-NC61-PadJ1)") (class "Default")
      (node (ref "U51") (pin "J1") (pinfunction "NC61_J1") (pintype "passive+no_connect"))
    )
    (net (code "115") (name "unconnected-(U51-NC62-PadJ2)") (class "Default")
      (node (ref "U51") (pin "J2") (pinfunction "NC62_J2") (pintype "passive+no_connect"))
    )
    (net (code "116") (name "unconnected-(U51-NC63-PadJ3)") (class "Default")
      (node (ref "U51") (pin "J3") (pinfunction "NC63_J3") (pintype "passive+no_connect"))
    )
    (net (code "117") (name "unconnected-(U51-NC64-PadJ12)") (class "Default")
      (node (ref "U51") (pin "J12") (pinfunction "NC64_J12") (pintype "passive+no_connect"))
    )
    (net (code "118") (name "unconnected-(U51-NC65-PadJ13)") (class "Default")
      (node (ref "U51") (pin "J13") (pinfunction "NC65_J13") (pintype "passive+no_connect"))
    )
    (net (code "119") (name "unconnected-(U51-NC66-PadJ14)") (class "Default")
      (node (ref "U51") (pin "J14") (pinfunction "NC66_J14") (pintype "passive+no_connect"))
    )
    (net (code "120") (name "unconnected-(U51-NC67-PadK1)") (class "Default")
      (node (ref "U51") (pin "K1") (pinfunction "NC67_K1") (pintype "passive+no_connect"))
    )
    (net (code "121") (name "unconnected-(U51-NC68-PadK2)") (class "Default")
      (node (ref "U51") (pin "K2") (pinfunction "NC68_K2") (pintype "passive+no_connect"))
    )
    (net (code "122") (name "unconnected-(U51-NC69-PadK3)") (class "Default")
      (node (ref "U51") (pin "K3") (pinfunction "NC69_K3") (pintype "passive+no_connect"))
    )
    (net (code "123") (name "unconnected-(U51-NC70-PadK12)") (class "Default")
      (node (ref "U51") (pin "K12") (pinfunction "NC70_K12") (pintype "passive+no_connect"))
    )
    (net (code "124") (name "unconnected-(U51-NC71-PadK13)") (class "Default")
      (node (ref "U51") (pin "K13") (pinfunction "NC71_K13") (pintype "passive+no_connect"))
    )
    (net (code "125") (name "unconnected-(U51-NC72-PadK14)") (class "Default")
      (node (ref "U51") (pin "K14") (pinfunction "NC72_K14") (pintype "passive+no_connect"))
    )
    (net (code "126") (name "unconnected-(U51-NC73-PadL1)") (class "Default")
      (node (ref "U51") (pin "L1") (pinfunction "NC73_L1") (pintype "passive+no_connect"))
    )
    (net (code "127") (name "unconnected-(U51-NC74-PadL2)") (class "Default")
      (node (ref "U51") (pin "L2") (pinfunction "NC74_L2") (pintype "passive+no_connect"))
    )
    (net (code "128") (name "unconnected-(U51-NC75-PadL3)") (class "Default")
      (node (ref "U51") (pin "L3") (pinfunction "NC75_L3") (pintype "passive+no_connect"))
    )
    (net (code "129") (name "unconnected-(U51-NC76-PadL12)") (class "Default")
      (node (ref "U51") (pin "L12") (pinfunction "NC76_L12") (pintype "passive+no_connect"))
    )
    (net (code "130") (name "unconnected-(U51-NC77-PadL13)") (class "Default")
      (node (ref "U51") (pin "L13") (pinfunction "NC77_L13") (pintype "passive+no_connect"))
    )
    (net (code "131") (name "unconnected-(U51-NC78-PadL14)") (class "Default")
      (node (ref "U51") (pin "L14") (pinfunction "NC78_L14") (pintype "passive+no_connect"))
    )
    (net (code "132") (name "unconnected-(U51-NC79-PadM1)") (class "Default")
      (node (ref "U51") (pin "M1") (pinfunction "NC79_M1") (pintype "passive+no_connect"))
    )
    (net (code "133") (name "unconnected-(U51-NC80-PadM2)") (class "Default")
      (node (ref "U51") (pin "M2") (pinfunction "NC80_M2") (pintype "passive+no_connect"))
    )
    (net (code "134") (name "unconnected-(U51-NC81-PadM3)") (class "Default")
      (node (ref "U51") (pin "M3") (pinfunction "NC81_M3") (pintype "passive+no_connect"))
    )
    (net (code "135") (name "unconnected-(U51-NC82-PadM7)") (class "Default")
      (node (ref "U51") (pin "M7") (pinfunction "NC82_M7") (pintype "passive+no_connect"))
    )
    (net (code "136") (name "unconnected-(U51-NC83-PadM8)") (class "Default")
      (node (ref "U51") (pin "M8") (pinfunction "NC83_M8") (pintype "passive+no_connect"))
    )
    (net (code "137") (name "unconnected-(U51-NC84-PadM9)") (class "Default")
      (node (ref "U51") (pin "M9") (pinfunction "NC84_M9") (pintype "passive+no_connect"))
    )
    (net (code "138") (name "unconnected-(U51-NC85-PadM10)") (class "Default")
      (node (ref "U51") (pin "M10") (pinfunction "NC85_M10") (pintype "passive+no_connect"))
    )
    (net (code "139") (name "unconnected-(U51-NC86-PadM11)") (class "Default")
      (node (ref "U51") (pin "M11") (pinfunction "NC86_M11") (pintype "passive+no_connect"))
    )
    (net (code "140") (name "unconnected-(U51-NC87-PadM12)") (class "Default")
      (node (ref "U51") (pin "M12") (pinfunction "NC87_M12") (pintype "passive+no_connect"))
    )
    (net (code "141") (name "unconnected-(U51-NC88-PadM13)") (class "Default")
      (node (ref "U51") (pin "M13") (pinfunction "NC88_M13") (pintype "passive+no_connect"))
    )
    (net (code "142") (name "unconnected-(U51-NC89-PadM14)") (class "Default")
      (node (ref "U51") (pin "M14") (pinfunction "NC89_M14") (pintype "passive+no_connect"))
    )
    (net (code "143") (name "unconnected-(U51-NC90-PadN1)") (class "Default")
      (node (ref "U51") (pin "N1") (pinfunction "NC90_N1") (pintype "passive+no_connect"))
    )
    (net (code "144") (name "unconnected-(U51-NC91-PadN3)") (class "Default")
      (node (ref "U51") (pin "N3") (pinfunction "NC91_N3") (pintype "passive+no_connect"))
    )
    (net (code "145") (name "unconnected-(U51-NC92-PadN6)") (class "Default")
      (node (ref "U51") (pin "N6") (pinfunction "NC92_N6") (pintype "passive+no_connect"))
    )
    (net (code "146") (name "unconnected-(U51-NC93-PadN7)") (class "Default")
      (node (ref "U51") (pin "N7") (pinfunction "NC93_N7") (pintype "passive+no_connect"))
    )
    (net (code "147") (name "unconnected-(U51-NC94-PadN8)") (class "Default")
      (node (ref "U51") (pin "N8") (pinfunction "NC94_N8") (pintype "passive+no_connect"))
    )
    (net (code "148") (name "unconnected-(U51-NC95-PadN9)") (class "Default")
      (node (ref "U51") (pin "N9") (pinfunction "NC95_N9") (pintype "passive+no_connect"))
    )
    (net (code "149") (name "unconnected-(U51-NC96-PadN10)") (class "Default")
      (node (ref "U51") (pin "N10") (pinfunction "NC96_N10") (pintype "passive+no_connect"))
    )
    (net (code "150") (name "unconnected-(U51-NC97-PadN11)") (class "Default")
      (node (ref "U51") (pin "N11") (pinfunction "NC97_N11") (pintype "passive+no_connect"))
    )
    (net (code "151") (name "unconnected-(U51-NC98-PadN12)") (class "Default")
      (node (ref "U51") (pin "N12") (pinfunction "NC98_N12") (pintype "passive+no_connect"))
    )
    (net (code "152") (name "unconnected-(U51-NC99-PadN13)") (class "Default")
      (node (ref "U51") (pin "N13") (pinfunction "NC99_N13") (pintype "passive+no_connect"))
    )
    (net (code "153") (name "unconnected-(U51-NC100-PadN14)") (class "Default")
      (node (ref "U51") (pin "N14") (pinfunction "NC100_N14") (pintype "passive+no_connect"))
    )
    (net (code "154") (name "unconnected-(U51-NC101-PadP1)") (class "Default")
      (node (ref "U51") (pin "P1") (pinfunction "NC101_P1") (pintype "passive+no_connect"))
    )
    (net (code "155") (name "unconnected-(U51-NC102-PadP2)") (class "Default")
      (node (ref "U51") (pin "P2") (pinfunction "NC102_P2") (pintype "passive+no_connect"))
    )
    (net (code "156") (name "unconnected-(U51-NC103-PadP7)") (class "Default")
      (node (ref "U51") (pin "P7") (pinfunction "NC103_P7") (pintype "passive+no_connect"))
    )
    (net (code "157") (name "unconnected-(U51-NC104-PadP8)") (class "Default")
      (node (ref "U51") (pin "P8") (pinfunction "NC104_P8") (pintype "passive+no_connect"))
    )
    (net (code "158") (name "unconnected-(U51-NC105-PadP9)") (class "Default")
      (node (ref "U51") (pin "P9") (pinfunction "NC105_P9") (pintype "passive+no_connect"))
    )
    (net (code "159") (name "unconnected-(U51-NC106-PadP11)") (class "Default")
      (node (ref "U51") (pin "P11") (pinfunction "NC106_P11") (pintype "passive+no_connect"))
    )
    (net (code "160") (name "unconnected-(U51-NC107-PadP12)") (class "Default")
      (node (ref "U51") (pin "P12") (pinfunction "NC107_P12") (pintype "passive+no_connect"))
    )
    (net (code "161") (name "unconnected-(U51-NC108-PadP13)") (class "Default")
      (node (ref "U51") (pin "P13") (pinfunction "NC108_P13") (pintype "passive+no_connect"))
    )
    (net (code "162") (name "unconnected-(U51-NC109-PadP14)") (class "Default")
      (node (ref "U51") (pin "P14") (pinfunction "NC109_P14") (pintype "passive+no_connect"))
    )
    (net (code "163") (name "unconnected-(U51-RFU1-PadA7)") (class "Default")
      (node (ref "U51") (pin "A7") (pinfunction "RFU1_A7") (pintype "passive"))
    )
    (net (code "164") (name "unconnected-(U51-RFU2-PadE5)") (class "Default")
      (node (ref "U51") (pin "E5") (pinfunction "RFU2_E5") (pintype "passive"))
    )
    (net (code "165") (name "unconnected-(U51-RFU3-PadE8)") (class "Default")
      (node (ref "U51") (pin "E8") (pinfunction "RFU3_E8") (pintype "passive"))
    )
    (net (code "166") (name "unconnected-(U51-RFU4-PadE9)") (class "Default")
      (node (ref "U51") (pin "E9") (pinfunction "RFU4_E9") (pintype "passive"))
    )
    (net (code "167") (name "unconnected-(U51-RFU5-PadE10)") (class "Default")
      (node (ref "U51") (pin "E10") (pinfunction "RFU5_E10") (pintype "passive"))
    )
    (net (code "168") (name "unconnected-(U51-RFU6-PadF10)") (class "Default")
      (node (ref "U51") (pin "F10") (pinfunction "RFU6_F10") (pintype "passive"))
    )
    (net (code "169") (name "unconnected-(U51-RFU7-PadG10)") (class "Default")
      (node (ref "U51") (pin "G10") (pinfunction "RFU7_G10") (pintype "passive"))
    )
    (net (code "170") (name "unconnected-(U51-RFU8-PadK6)") (class "Default")
      (node (ref "U51") (pin "K6") (pinfunction "RFU8_K6") (pintype "passive"))
    )
    (net (code "171") (name "unconnected-(U51-RFU9-PadK7)") (class "Default")
      (node (ref "U51") (pin "K7") (pinfunction "RFU9_K7") (pintype "passive"))
    )
    (net (code "172") (name "unconnected-(U51-RFU10-PadK10)") (class "Default")
      (node (ref "U51") (pin "K10") (pinfunction "RFU10_K10") (pintype "passive"))
    )
    (net (code "173") (name "unconnected-(U51-RFU11-PadP10)") (class "Default")
      (node (ref "U51") (pin "P10") (pinfunction "RFU11_P10") (pintype "passive"))
    )
  )
)
